# Soldeerbout_P2.net
KiCad netlist of a schematic drawn in Altium Designer
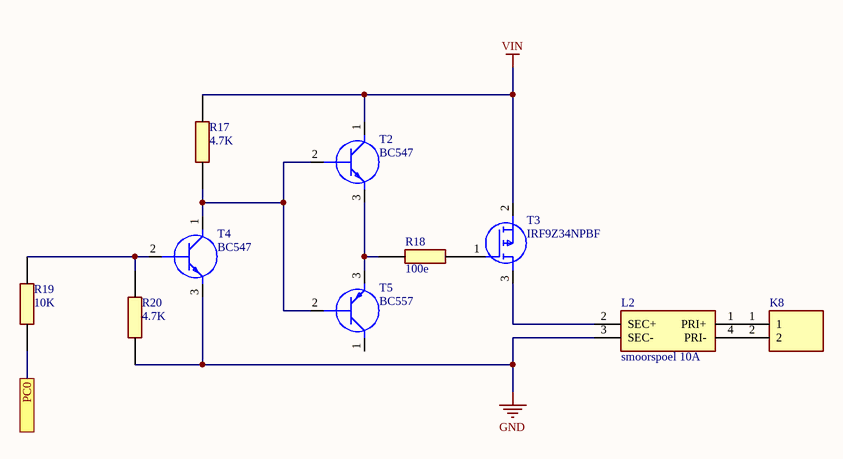
[diagram p0: Soldeerbout_P2.SchDoc]

(export (version "E")
  (design (tool "Eeschema 10.0.6"))
  (components
    (comp (ref "K8")
      (value "~")
      (footprint "SamacSys:K printkroonsteen 5.08")
      (description "Connector")
      (fields
        (field (name "MOUSER2 PART NUMBER") "490-TB007-508-02BE")
        (field (name "MANUFACTURER_PART_NUMBER") "TB007-508-02BE")
      )
      (libsource (lib "SamacSys") (part "TB007-508-02BE"))
    )
    (comp (ref "L2")
      (value "smoorspoel 10A")
      (footprint "SamacSys:CM smoorspoelen/filters 170ohm 100Mhz 10A")
      (description "Transformer")
      (fields (field (name "MANUFACTURER_PART_NUMBER") "CM2545X171B-10"))
      (libsource (lib "SamacSys") (part "CM2545X171B-10"))
    )
    (comp (ref "R17")
      (value "4.7K")
      (footprint "SamacSys:0805")
      (description "Resistor")
      (fields (field (name "MANUFACTURER_PART_NUMBER") "ESR10EZPJ183"))
      (libsource (lib "") (part "ESR10EZPJ183_1"))
    )
    (comp (ref "R18")
      (value "100e")
      (footprint "SamacSys:0805")
      (description "Resistor")
      (fields (field (name "MANUFACTURER_PART_NUMBER") "ESR10EZPJ183"))
      (libsource (lib "SamacSys") (part "ESR10EZPJ183"))
    )
    (comp (ref "R19")
      (value "10K")
      (footprint "SamacSys:0805")
      (description "Resistor")
      (fields (field (name "MANUFACTURER_PART_NUMBER") "ESR10EZPJ183"))
      (libsource (lib "") (part "ESR10EZPJ183_1"))
    )
    (comp (ref "R20")
      (value "4.7K")
      (footprint "SamacSys:0805")
      (description "Resistor")
      (fields (field (name "MANUFACTURER_PART_NUMBER") "ESR10EZPJ183"))
      (libsource (lib "") (part "ESR10EZPJ183_1"))
    )
    (comp (ref "T2")
      (value "BC547")
      (footprint "SamacSys:T1,2,4 BC547C 45V 100mA")
      (description "Transistor BJT NPN")
      (fields (field (name "MANUFACTURER_PART_NUMBER") "BC547CBU"))
      (libsource (lib "SamacSys") (part "BC547CBU"))
    )
    (comp (ref "T3")
      (value "IRF9Z34NPBF")
      (footprint "SamacSys:T3 P-mosfet 55V 17A 0.1e")
      (description "MOSFET (P-Channel)")
      (fields (field (name "MOUSER2 PART NUMBER") "942-IRF9Z34NPBF"))
      (libsource (lib "SamacSys") (part "IRF9Z34NPBF"))
    )
    (comp (ref "T4")
      (value "BC547")
      (footprint "SamacSys:T1,2,4 BC547C 45V 100mA")
      (description "Transistor BJT NPN")
      (fields (field (name "MANUFACTURER_PART_NUMBER") "BC547CBU"))
      (libsource (lib "SamacSys") (part "BC547CBU"))
    )
    (comp (ref "T5")
      (value "BC557")
      (footprint "SamacSys:BC557C T5 45V 100mA")
      (description "Transistor BJT PNP")
      (fields
        (field (name "MOUSER2 PART NUMBER") "512-BC557ATA")
        (field (name "MANUFACTURER_PART_NUMBER") "BC557ATA")
      )
      (libsource (lib "SamacSys") (part "BC557ATA"))
    )
  )
  (nets
    (net (code "1") (name "/PC0") (class "Default")
      (node (ref "R19") (pin "2") (pinfunction "2_2") (pintype "passive"))
    )
    (net (code "2") (name "GND") (class "Default")
      (node (ref "L2") (pin "3") (pinfunction "SEC-_3") (pintype "passive"))
      (node (ref "R20") (pin "2") (pinfunction "2_2") (pintype "passive"))
      (node (ref "T4") (pin "3") (pinfunction "E_3") (pintype "passive"))
    )
    (net (code "3") (name "Net-(L2-PRI+)") (class "Default")
      (node (ref "K8") (pin "1") (pinfunction "1_1") (pintype "passive"))
      (node (ref "L2") (pin "1") (pinfunction "PRI+_1") (pintype "passive"))
    )
    (net (code "4") (name "Net-(L2-PRI-)") (class "Default")
      (node (ref "K8") (pin "2") (pinfunction "2_2") (pintype "passive"))
      (node (ref "L2") (pin "4") (pinfunction "PRI-_4") (pintype "passive"))
    )
    (net (code "5") (name "Net-(L2-SEC+)") (class "Default")
      (node (ref "L2") (pin "2") (pinfunction "SEC+_2") (pintype "passive"))
      (node (ref "T3") (pin "3") (pinfunction "D_3") (pintype "passive"))
    )
    (net (code "6") (name "Net-(T2-B)") (class "Default")
      (node (ref "R17") (pin "2") (pinfunction "2_2") (pintype "passive"))
      (node (ref "T2") (pin "2") (pinfunction "B_2") (pintype "passive"))
      (node (ref "T4") (pin "1") (pinfunction "C_1") (pintype "passive"))
      (node (ref "T5") (pin "2") (pinfunction "B_2") (pintype "passive"))
    )
    (net (code "7") (name "Net-(T2-E)") (class "Default")
      (node (ref "R18") (pin "1") (pinfunction "1_1") (pintype "passive"))
      (node (ref "T2") (pin "3") (pinfunction "E_3") (pintype "passive"))
      (node (ref "T5") (pin "3") (pinfunction "E_3") (pintype "passive"))
    )
    (net (code "8") (name "Net-(T3-G)") (class "Default")
      (node (ref "R18") (pin "2") (pinfunction "2_2") (pintype "passive"))
      (node (ref "T3") (pin "1") (pinfunction "G_1") (pintype "passive"))
    )
    (net (code "9") (name "Net-(T4-B)") (class "Default")
      (node (ref "R19") (pin "1") (pinfunction "1_1") (pintype "passive"))
      (node (ref "R20") (pin "1") (pinfunction "1_1") (pintype "passive"))
      (node (ref "T4") (pin "2") (pinfunction "B_2") (pintype "passive"))
    )
    (net (code "10") (name "VIN") (class "Default")
      (node (ref "R17") (pin "1") (pinfunction "1_1") (pintype "passive"))
      (node (ref "T2") (pin "1") (pinfunction "C_1") (pintype "passive"))
      (node (ref "T3") (pin "2") (pinfunction "S_2") (pintype "passive"))
    )
    (net (code "11") (name "unconnected-(T5-C-Pad1)") (class "Default")
      (node (ref "T5") (pin "1") (pinfunction "C_1") (pintype "passive"))
    )
  )
)
